# Sheet2.net
KiCad netlist of a schematic drawn in Altium Designer
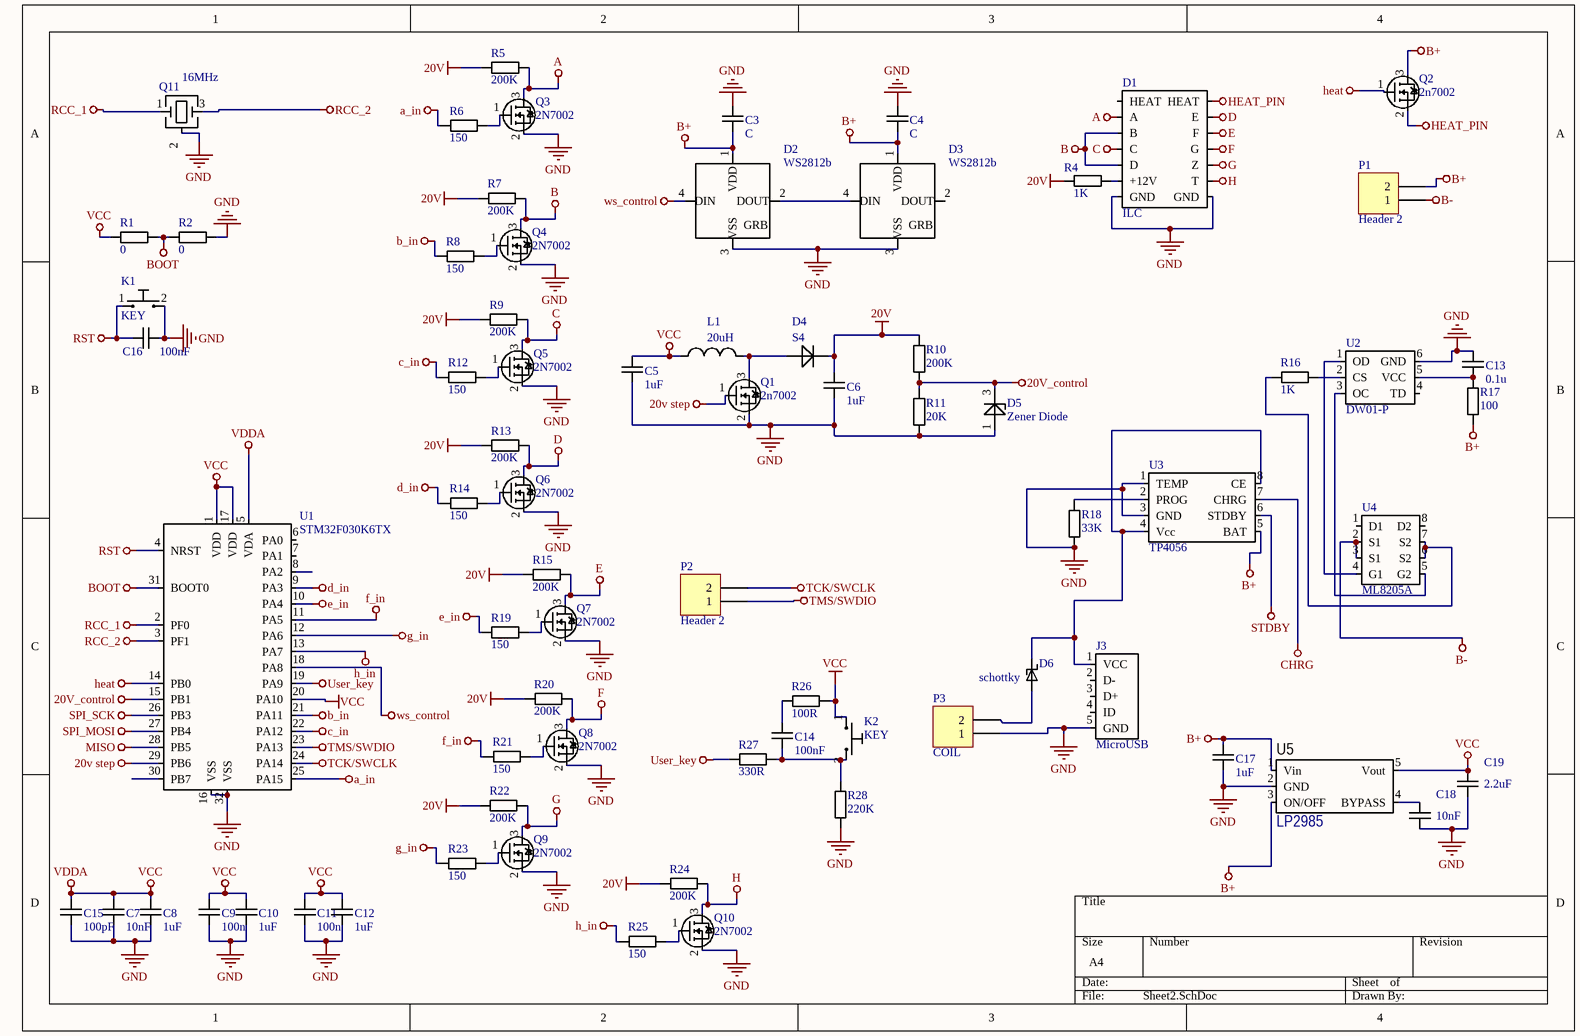
[diagram p0: Sheet2.SchDoc]

(export (version "E")
  (design (tool "Eeschema 10.0.6"))
  (components
    (comp (ref "C3") (value "C") (footprint "SMD-0402C") (libsource (lib "Schlib2") (part "С")))
    (comp (ref "C4") (value "C") (footprint "SMD-0402C") (libsource (lib "Schlib2") (part "С")))
    (comp (ref "C5") (value "1uF") (footprint "SMD-0402C") (libsource (lib "Schlib2") (part "С")))
    (comp (ref "C6") (value "1uF") (footprint "SMD-1206C") (libsource (lib "Schlib2") (part "С")))
    (comp (ref "C7") (value "10nF") (footprint "SMD-0402C") (libsource (lib "Schlib2") (part "С")))
    (comp (ref "C8") (value "1uF") (footprint "SMD-0402C") (libsource (lib "Schlib2") (part "С")))
    (comp (ref "C9") (value "100n") (footprint "SMD-0402C") (libsource (lib "Schlib2") (part "С")))
    (comp (ref "C10") (value "1uF") (footprint "SMD-0402C") (libsource (lib "Schlib2") (part "С")))
    (comp (ref "C11") (value "100n") (footprint "SMD-0402C") (libsource (lib "Schlib2") (part "С")))
    (comp (ref "C12") (value "1uF") (footprint "SMD-0402C") (libsource (lib "Schlib2") (part "С")))
    (comp (ref "C13") (value "0.1u") (footprint "SMD-0402C") (libsource (lib "Schlib2") (part "С")))
    (comp (ref "C14") (value "100nF") (footprint "SMD-0402C") (libsource (lib "Schlib2") (part "С")))
    (comp (ref "C15") (value "100pF") (footprint "SMD-0402C") (libsource (lib "Schlib2") (part "С")))
    (comp (ref "C16") (value "100nF") (footprint "SMD-0402C") (libsource (lib "Schlib2") (part "С")))
    (comp (ref "C17") (value "1uF") (footprint "SMD-0402C") (libsource (lib "Schlib2") (part "С")))
    (comp (ref "C18") (value "10nF") (footprint "SMD-0402C") (libsource (lib "Schlib2") (part "С")))
    (comp (ref "C19") (value "2.2uF") (footprint "SMD-0402C") (libsource (lib "Schlib2") (part "С")))
    (comp (ref "D1") (value "ILC") (footprint "ILC_1") (libsource (lib "Schlib2") (part "ILC-1.9")))
    (comp (ref "D2") (value "WS2812b") (footprint "WS2812b") (libsource (lib "Schlib2") (part "WS2812b")))
    (comp (ref "D3") (value "WS2812b") (footprint "WS2812b") (libsource (lib "Schlib2") (part "WS2812b")))
    (comp (ref "D4") (value "S4") (footprint "S4") (libsource (lib "Schlib2") (part "Diode")))
    (comp (ref "D5") (value "Zener Diode") (footprint "2n7002") (libsource (lib "Schlib2") (part "BZX84")))
    (comp (ref "D6") (value "schottky") (footprint "DO-214AC") (libsource (lib "Schlib2") (part "SS14")))
    (comp (ref "J3")
      (value "MicroUSB")
      (footprint "Micro USB")
      (libsource (lib "Schlib2") (part "Micro_USB_female"))
    )
    (comp (ref "K1") (value "KEY") (footprint "KEY") (libsource (lib "Schlib2") (part "KEY")))
    (comp (ref "K2") (value "KEY") (footprint "KEY") (libsource (lib "Schlib2") (part "KEY")))
    (comp (ref "L1") (value "20uH") (footprint "L_0805") (libsource (lib "Schlib2") (part "L")))
    (comp (ref "P1")
      (value "Header 2")
      (footprint "2pin_battarery")
      (description "Header, 2-Pin")
      (fields (field (name "PUBLISHER") "Altium Limited"))
      (libsource (lib "Miscellaneous Connectors") (part "Header 2"))
    )
    (comp (ref "P2")
      (value "Header 2")
      (footprint "2pin_connector")
      (description "Header, 2-Pin")
      (fields (field (name "PUBLISHER") "Altium Limited"))
      (libsource (lib "Miscellaneous Connectors") (part "Header 2"))
    )
    (comp (ref "P3")
      (value "COIL")
      (footprint "2pin_connector")
      (description "Header, 2-Pin")
      (fields (field (name "PUBLISHER") "Altium Limited"))
      (libsource (lib "Miscellaneous Connectors") (part "Header 2"))
    )
    (comp (ref "Q1") (value "2n7002") (footprint "2n7002") (libsource (lib "Schlib2") (part "2n7002")))
    (comp (ref "Q2") (value "2n7002") (footprint "2n7002") (libsource (lib "Schlib2") (part "2n7002")))
    (comp (ref "Q3") (value "2N7002") (footprint "2n7002") (libsource (lib "Schlib2") (part "2n7002")))
    (comp (ref "Q4") (value "2N7002") (footprint "2n7002") (libsource (lib "Schlib2") (part "2n7002")))
    (comp (ref "Q5") (value "2N7002") (footprint "2n7002") (libsource (lib "Schlib2") (part "2n7002")))
    (comp (ref "Q6") (value "2N7002") (footprint "2n7002") (libsource (lib "Schlib2") (part "2n7002")))
    (comp (ref "Q7") (value "2N7002") (footprint "2n7002") (libsource (lib "Schlib2") (part "2n7002")))
    (comp (ref "Q8") (value "2N7002") (footprint "2n7002") (libsource (lib "Schlib2") (part "2n7002")))
    (comp (ref "Q9") (value "2N7002") (footprint "2n7002") (libsource (lib "Schlib2") (part "2n7002")))
    (comp (ref "Q10") (value "2N7002") (footprint "2n7002") (libsource (lib "Schlib2") (part "2n7002")))
    (comp (ref "Q11")
      (value "16MHz")
      (footprint "Murata Ceramic Resonator")
      (libsource (lib "Schlib2") (part "Crystal_3"))
    )
    (comp (ref "R1") (value "0") (footprint "SMD-0402-RES") (libsource (lib "Schlib2") (part "R")))
    (comp (ref "R2") (value "0") (footprint "SMD-0402-RES") (libsource (lib "Schlib2") (part "R")))
    (comp (ref "R4") (value "1K") (footprint "SMD-0402-RES") (libsource (lib "Schlib2") (part "R")))
    (comp (ref "R5") (value "200K") (footprint "SMD-0402-RES") (libsource (lib "Schlib2") (part "R")))
    (comp (ref "R6") (value "150") (footprint "SMD-0402-RES") (libsource (lib "Schlib2") (part "R")))
    (comp (ref "R7") (value "200K") (footprint "SMD-0402-RES") (libsource (lib "Schlib2") (part "R")))
    (comp (ref "R8") (value "150") (footprint "SMD-0402-RES") (libsource (lib "Schlib2") (part "R")))
    (comp (ref "R9") (value "200K") (footprint "SMD-0402-RES") (libsource (lib "Schlib2") (part "R")))
    (comp (ref "R10") (value "200K") (footprint "SMD-0402-RES") (libsource (lib "Schlib2") (part "R")))
    (comp (ref "R11") (value "20K") (footprint "SMD-0402-RES") (libsource (lib "Schlib2") (part "R")))
    (comp (ref "R12") (value "150") (footprint "SMD-0402-RES") (libsource (lib "Schlib2") (part "R")))
    (comp (ref "R13") (value "200K") (footprint "SMD-0402-RES") (libsource (lib "Schlib2") (part "R")))
    (comp (ref "R14") (value "150") (footprint "SMD-0402-RES") (libsource (lib "Schlib2") (part "R")))
    (comp (ref "R15") (value "200K") (footprint "SMD-0402-RES") (libsource (lib "Schlib2") (part "R")))
    (comp (ref "R16") (value "1K") (footprint "SMD-0402-RES") (libsource (lib "Schlib2") (part "R")))
    (comp (ref "R17") (value "100") (footprint "SMD-0402-RES") (libsource (lib "Schlib2") (part "R")))
    (comp (ref "R18") (value "33K") (footprint "SMD-0402-RES") (libsource (lib "Schlib2") (part "R")))
    (comp (ref "R19") (value "150") (footprint "SMD-0402-RES") (libsource (lib "Schlib2") (part "R")))
    (comp (ref "R20") (value "200K") (footprint "SMD-0402-RES") (libsource (lib "Schlib2") (part "R")))
    (comp (ref "R21") (value "150") (footprint "SMD-0402-RES") (libsource (lib "Schlib2") (part "R")))
    (comp (ref "R22") (value "200K") (footprint "SMD-0402-RES") (libsource (lib "Schlib2") (part "R")))
    (comp (ref "R23") (value "150") (footprint "SMD-0402-RES") (libsource (lib "Schlib2") (part "R")))
    (comp (ref "R24") (value "200K") (footprint "SMD-0402-RES") (libsource (lib "Schlib2") (part "R")))
    (comp (ref "R25") (value "150") (footprint "SMD-0402-RES") (libsource (lib "Schlib2") (part "R")))
    (comp (ref "R26") (value "100R") (footprint "SMD-0402-RES") (libsource (lib "Schlib2") (part "R")))
    (comp (ref "R27") (value "330R") (footprint "SMD-0402-RES") (libsource (lib "Schlib2") (part "R")))
    (comp (ref "R28") (value "220K") (footprint "SMD-0402-RES") (libsource (lib "Schlib2") (part "R")))
    (comp (ref "U1")
      (value "STM32F030K6TX")
      (footprint "LQFP-32")
      (libsource (lib "Schlib2") (part "STM32F030K6TX"))
    )
    (comp (ref "U2") (value "DW01-P") (footprint "SOT-23-6") (libsource (lib "Schlib2") (part "DW01-P")))
    (comp (ref "U3")
      (value "TP4056")
      (footprint "SOIC8")
      (description "1A Standalone Linear Li-lon Battery Charger with Thermal\r\nRegulation in SOP-8")
      (libsource (lib "Schlib2") (part "TP4056"))
    )
    (comp (ref "U4")
      (value "ML8205A")
      (footprint "TSSOP-8")
      (description "The ML8205A uses advanced trench technology to")
      (libsource (lib "Schlib2") (part "ML8205A"))
    )
    (comp (ref "U5") (value "LP2985") (footprint "SOT-23-5") (libsource (lib "Schlib2") (part "LP2985")))
  )
  (nets
    (net (code "1") (name "20V") (class "Default")
      (node (ref "C6") (pin "1") (pinfunction "1_1") (pintype "passive"))
      (node (ref "D4") (pin "2") (pinfunction "2_2") (pintype "passive"))
      (node (ref "R10") (pin "1") (pinfunction "1_1") (pintype "passive"))
      (node (ref "R13") (pin "2") (pinfunction "2_2") (pintype "passive"))
      (node (ref "R15") (pin "2") (pinfunction "2_2") (pintype "passive"))
      (node (ref "R20") (pin "2") (pinfunction "2_2") (pintype "passive"))
      (node (ref "R22") (pin "2") (pinfunction "2_2") (pintype "passive"))
      (node (ref "R24") (pin "2") (pinfunction "2_2") (pintype "passive"))
      (node (ref "R4") (pin "1") (pinfunction "1_1") (pintype "passive"))
      (node (ref "R5") (pin "2") (pinfunction "2_2") (pintype "passive"))
      (node (ref "R7") (pin "2") (pinfunction "2_2") (pintype "passive"))
      (node (ref "R9") (pin "2") (pinfunction "2_2") (pintype "passive"))
    )
    (net (code "2") (name "20V_control") (class "Default")
      (node (ref "D5") (pin "3") (pinfunction "3_3") (pintype "passive"))
      (node (ref "R10") (pin "2") (pinfunction "2_2") (pintype "passive"))
      (node (ref "R11") (pin "2") (pinfunction "2_2") (pintype "passive"))
      (node (ref "U1") (pin "15") (pinfunction "PB1_15") (pintype "passive"))
    )
    (net (code "3") (name "20v step") (class "Default")
      (node (ref "Q1") (pin "1") (pinfunction "1_1") (pintype "passive"))
      (node (ref "U1") (pin "29") (pinfunction "PB6_29") (pintype "passive"))
    )
    (net (code "4") (name "A") (class "Default")
      (node (ref "D1") (pin "2") (pinfunction "A_2") (pintype "passive"))
      (node (ref "Q3") (pin "3") (pinfunction "3_3") (pintype "passive"))
      (node (ref "R5") (pin "1") (pinfunction "1_1") (pintype "passive"))
    )
    (net (code "5") (name "B") (class "Default")
      (node (ref "D1") (pin "3") (pinfunction "B_3") (pintype "passive"))
      (node (ref "D1") (pin "5") (pinfunction "D_5") (pintype "passive"))
      (node (ref "Q4") (pin "3") (pinfunction "3_3") (pintype "passive"))
      (node (ref "R7") (pin "1") (pinfunction "1_1") (pintype "passive"))
    )
    (net (code "6") (name "B+") (class "Default")
      (node (ref "C17") (pin "2") (pinfunction "2_2") (pintype "passive"))
      (node (ref "C3") (pin "1") (pinfunction "1_1") (pintype "passive"))
      (node (ref "C4") (pin "2") (pinfunction "2_2") (pintype "passive"))
      (node (ref "D2") (pin "1") (pinfunction "VDD_1") (pintype "passive"))
      (node (ref "D3") (pin "1") (pinfunction "VDD_1") (pintype "passive"))
      (node (ref "P1") (pin "2") (pinfunction "2_2") (pintype "passive"))
      (node (ref "Q2") (pin "3") (pinfunction "3_3") (pintype "passive"))
      (node (ref "R17") (pin "2") (pinfunction "2_2") (pintype "passive"))
      (node (ref "U3") (pin "5") (pinfunction "BAT_5") (pintype "passive"))
      (node (ref "U5") (pin "1") (pinfunction "Vin_1") (pintype "passive"))
      (node (ref "U5") (pin "3") (pinfunction "ON/OFF_3") (pintype "passive"))
    )
    (net (code "7") (name "B-") (class "Default")
      (node (ref "P1") (pin "1") (pinfunction "1_1") (pintype "passive"))
      (node (ref "U4") (pin "2") (pinfunction "S1_2") (pintype "passive"))
      (node (ref "U4") (pin "3") (pinfunction "S1_3") (pintype "passive"))
    )
    (net (code "8") (name "BOOT") (class "Default")
      (node (ref "R1") (pin "2") (pinfunction "2_2") (pintype "passive"))
      (node (ref "R2") (pin "1") (pinfunction "1_1") (pintype "passive"))
      (node (ref "U1") (pin "31") (pinfunction "BOOT0_31") (pintype "passive"))
    )
    (net (code "9") (name "C") (class "Default")
      (node (ref "D1") (pin "4") (pinfunction "C_4") (pintype "passive"))
      (node (ref "Q5") (pin "3") (pinfunction "3_3") (pintype "passive"))
      (node (ref "R9") (pin "1") (pinfunction "1_1") (pintype "passive"))
    )
    (net (code "10") (name "CHRG") (class "Default")
      (node (ref "U3") (pin "7") (pinfunction "CHRG_7") (pintype "passive"))
    )
    (net (code "11") (name "D") (class "Default")
      (node (ref "D1") (pin "13") (pinfunction "E_13") (pintype "passive"))
      (node (ref "Q6") (pin "3") (pinfunction "3_3") (pintype "passive"))
      (node (ref "R13") (pin "1") (pinfunction "1_1") (pintype "passive"))
    )
    (net (code "12") (name "E") (class "Default")
      (node (ref "D1") (pin "12") (pinfunction "F_12") (pintype "passive"))
      (node (ref "Q7") (pin "3") (pinfunction "3_3") (pintype "passive"))
      (node (ref "R15") (pin "1") (pinfunction "1_1") (pintype "passive"))
    )
    (net (code "13") (name "F") (class "Default")
      (node (ref "D1") (pin "11") (pinfunction "G_11") (pintype "passive"))
      (node (ref "Q8") (pin "3") (pinfunction "3_3") (pintype "passive"))
      (node (ref "R20") (pin "1") (pinfunction "1_1") (pintype "passive"))
    )
    (net (code "14") (name "G") (class "Default")
      (node (ref "D1") (pin "10") (pinfunction "Z_10") (pintype "passive"))
      (node (ref "Q9") (pin "3") (pinfunction "3_3") (pintype "passive"))
      (node (ref "R22") (pin "1") (pinfunction "1_1") (pintype "passive"))
    )
    (net (code "15") (name "GND") (class "Default")
      (node (ref "C10") (pin "1") (pinfunction "1_1") (pintype "passive"))
      (node (ref "C11") (pin "2") (pinfunction "2_2") (pintype "passive"))
      (node (ref "C12") (pin "1") (pinfunction "1_1") (pintype "passive"))
      (node (ref "C13") (pin "2") (pinfunction "2_2") (pintype "passive"))
      (node (ref "C15") (pin "1") (pinfunction "1_1") (pintype "passive"))
      (node (ref "C16") (pin "2") (pinfunction "2_2") (pintype "passive"))
      (node (ref "C17") (pin "1") (pinfunction "1_1") (pintype "passive"))
      (node (ref "C18") (pin "1") (pinfunction "1_1") (pintype "passive"))
      (node (ref "C19") (pin "1") (pinfunction "1_1") (pintype "passive"))
      (node (ref "C3") (pin "2") (pinfunction "2_2") (pintype "passive"))
      (node (ref "C4") (pin "1") (pinfunction "1_1") (pintype "passive"))
      (node (ref "C5") (pin "1") (pinfunction "1_1") (pintype "passive"))
      (node (ref "C6") (pin "2") (pinfunction "2_2") (pintype "passive"))
      (node (ref "C7") (pin "2") (pinfunction "2_2") (pintype "passive"))
      (node (ref "C8") (pin "1") (pinfunction "1_1") (pintype "passive"))
      (node (ref "C9") (pin "2") (pinfunction "2_2") (pintype "passive"))
      (node (ref "D1") (pin "7") (pinfunction "GND_7") (pintype "passive"))
      (node (ref "D1") (pin "8") (pinfunction "GND_8") (pintype "passive"))
      (node (ref "D2") (pin "3") (pinfunction "VSS_3") (pintype "passive"))
      (node (ref "D3") (pin "3") (pinfunction "VSS_3") (pintype "passive"))
      (node (ref "D5") (pin "1") (pinfunction "1_1") (pintype "passive"))
      (node (ref "J3") (pin "5") (pinfunction "GND_5") (pintype "passive"))
      (node (ref "K1") (pin "2") (pinfunction "2_2") (pintype "passive"))
      (node (ref "P3") (pin "1") (pinfunction "1_1") (pintype "passive"))
      (node (ref "Q1") (pin "2") (pinfunction "2_2") (pintype "passive"))
      (node (ref "Q10") (pin "2") (pinfunction "2_2") (pintype "passive"))
      (node (ref "Q11") (pin "2") (pinfunction "2_2") (pintype "passive"))
      (node (ref "Q3") (pin "2") (pinfunction "2_2") (pintype "passive"))
      (node (ref "Q4") (pin "2") (pinfunction "2_2") (pintype "passive"))
      (node (ref "Q5") (pin "2") (pinfunction "2_2") (pintype "passive"))
      (node (ref "Q6") (pin "2") (pinfunction "2_2") (pintype "passive"))
      (node (ref "Q7") (pin "2") (pinfunction "2_2") (pintype "passive"))
      (node (ref "Q8") (pin "2") (pinfunction "2_2") (pintype "passive"))
      (node (ref "Q9") (pin "2") (pinfunction "2_2") (pintype "passive"))
      (node (ref "R11") (pin "1") (pinfunction "1_1") (pintype "passive"))
      (node (ref "R18") (pin "1") (pinfunction "1_1") (pintype "passive"))
      (node (ref "R2") (pin "2") (pinfunction "2_2") (pintype "passive"))
      (node (ref "R28") (pin "1") (pinfunction "1_1") (pintype "passive"))
      (node (ref "U1") (pin "16") (pinfunction "VSS_16") (pintype "passive"))
      (node (ref "U1") (pin "32") (pinfunction "VSS_32") (pintype "passive"))
      (node (ref "U2") (pin "6") (pinfunction "GND_6") (pintype "passive"))
      (node (ref "U3") (pin "1") (pinfunction "TEMP_1") (pintype "passive"))
      (node (ref "U3") (pin "3") (pinfunction "GND_3") (pintype "passive"))
      (node (ref "U5") (pin "2") (pinfunction "GND_2") (pintype "passive"))
    )
    (net (code "16") (name "H") (class "Default")
      (node (ref "D1") (pin "9") (pinfunction "T_9") (pintype "passive"))
      (node (ref "Q10") (pin "3") (pinfunction "3_3") (pintype "passive"))
      (node (ref "R24") (pin "1") (pinfunction "1_1") (pintype "passive"))
    )
    (net (code "17") (name "HEAT_PIN") (class "Default")
      (node (ref "D1") (pin "14") (pinfunction "HEAT_14") (pintype "passive"))
      (node (ref "Q2") (pin "2") (pinfunction "2_2") (pintype "passive"))
    )
    (net (code "18") (name "MISO") (class "Default")
      (node (ref "U1") (pin "28") (pinfunction "PB5_28") (pintype "passive"))
    )
    (net (code "19") (name "Net-(C14-Pad1)") (class "Default")
      (node (ref "C14") (pin "1") (pinfunction "1_1") (pintype "passive"))
      (node (ref "K2") (pin "2") (pinfunction "2_2") (pintype "passive"))
      (node (ref "R27") (pin "2") (pinfunction "2_2") (pintype "passive"))
      (node (ref "R28") (pin "2") (pinfunction "2_2") (pintype "passive"))
    )
    (net (code "20") (name "Net-(C14-Pad2)") (class "Default")
      (node (ref "C14") (pin "2") (pinfunction "2_2") (pintype "passive"))
      (node (ref "R26") (pin "1") (pinfunction "1_1") (pintype "passive"))
    )
    (net (code "21") (name "Net-(D1-+12V)") (class "Default")
      (node (ref "D1") (pin "6") (pinfunction "+12V_6") (pintype "passive"))
      (node (ref "R4") (pin "2") (pinfunction "2_2") (pintype "passive"))
    )
    (net (code "22") (name "Net-(D2-DOUT)") (class "Default")
      (node (ref "D2") (pin "2") (pinfunction "DOUT_2") (pintype "passive"))
      (node (ref "D3") (pin "4") (pinfunction "DIN_4") (pintype "passive"))
    )
    (net (code "23") (name "Net-(D4-Pad1)") (class "Default")
      (node (ref "D4") (pin "1") (pinfunction "1_1") (pintype "passive"))
      (node (ref "L1") (pin "2") (pinfunction "2_2") (pintype "passive"))
      (node (ref "Q1") (pin "3") (pinfunction "3_3") (pintype "passive"))
    )
    (net (code "24") (name "Net-(D6-PadA)") (class "Default")
      (node (ref "D6") (pin "A") (pinfunction "A_A") (pintype "passive"))
      (node (ref "P3") (pin "2") (pinfunction "2_2") (pintype "passive"))
    )
    (net (code "25") (name "Net-(J3-VCC)") (class "Default")
      (node (ref "D6") (pin "K") (pinfunction "K_K") (pintype "passive"))
      (node (ref "J3") (pin "1") (pinfunction "VCC_1") (pintype "passive"))
      (node (ref "U3") (pin "4") (pinfunction "Vcc_4") (pintype "passive"))
      (node (ref "U3") (pin "8") (pinfunction "CE_8") (pintype "passive"))
    )
    (net (code "26") (name "Net-(Q3-Pad1)") (class "Default")
      (node (ref "Q3") (pin "1") (pinfunction "1_1") (pintype "passive"))
      (node (ref "R6") (pin "1") (pinfunction "1_1") (pintype "passive"))
    )
    (net (code "27") (name "Net-(Q4-Pad1)") (class "Default")
      (node (ref "Q4") (pin "1") (pinfunction "1_1") (pintype "passive"))
      (node (ref "R8") (pin "1") (pinfunction "1_1") (pintype "passive"))
    )
    (net (code "28") (name "Net-(Q5-Pad1)") (class "Default")
      (node (ref "Q5") (pin "1") (pinfunction "1_1") (pintype "passive"))
      (node (ref "R12") (pin "1") (pinfunction "1_1") (pintype "passive"))
    )
    (net (code "29") (name "Net-(Q6-Pad1)") (class "Default")
      (node (ref "Q6") (pin "1") (pinfunction "1_1") (pintype "passive"))
      (node (ref "R14") (pin "1") (pinfunction "1_1") (pintype "passive"))
    )
    (net (code "30") (name "Net-(Q7-Pad1)") (class "Default")
      (node (ref "Q7") (pin "1") (pinfunction "1_1") (pintype "passive"))
      (node (ref "R19") (pin "1") (pinfunction "1_1") (pintype "passive"))
    )
    (net (code "31") (name "Net-(Q8-Pad1)") (class "Default")
      (node (ref "Q8") (pin "1") (pinfunction "1_1") (pintype "passive"))
      (node (ref "R21") (pin "1") (pinfunction "1_1") (pintype "passive"))
    )
    (net (code "32") (name "Net-(Q9-Pad1)") (class "Default")
      (node (ref "Q9") (pin "1") (pinfunction "1_1") (pintype "passive"))
      (node (ref "R23") (pin "1") (pinfunction "1_1") (pintype "passive"))
    )
    (net (code "33") (name "Net-(Q10-Pad1)") (class "Default")
      (node (ref "Q10") (pin "1") (pinfunction "1_1") (pintype "passive"))
      (node (ref "R25") (pin "1") (pinfunction "1_1") (pintype "passive"))
    )
    (net (code "34") (name "Net-(R16-Pad2)") (class "Default")
      (node (ref "R16") (pin "2") (pinfunction "2_2") (pintype "passive"))
      (node (ref "U4") (pin "6") (pinfunction "S2_6") (pintype "passive"))
      (node (ref "U4") (pin "7") (pinfunction "S2_7") (pintype "passive"))
    )
    (net (code "35") (name "Net-(U2-CS)") (class "Default")
      (node (ref "R16") (pin "1") (pinfunction "1_1") (pintype "passive"))
      (node (ref "U2") (pin "2") (pinfunction "CS_2") (pintype "passive"))
    )
    (net (code "36") (name "Net-(U2-OC)") (class "Default")
      (node (ref "U2") (pin "3") (pinfunction "OC_3") (pintype "passive"))
      (node (ref "U4") (pin "5") (pinfunction "G2_5") (pintype "passive"))
    )
    (net (code "37") (name "Net-(U2-OD)") (class "Default")
      (node (ref "U2") (pin "1") (pinfunction "OD_1") (pintype "passive"))
      (node (ref "U4") (pin "4") (pinfunction "G1_4") (pintype "passive"))
    )
    (net (code "38") (name "Net-(U2-VCC)") (class "Default")
      (node (ref "C13") (pin "1") (pinfunction "1_1") (pintype "passive"))
      (node (ref "R17") (pin "1") (pinfunction "1_1") (pintype "passive"))
      (node (ref "U2") (pin "5") (pinfunction "VCC_5") (pintype "passive"))
    )
    (net (code "39") (name "Net-(U3-PROG)") (class "Default")
      (node (ref "R18") (pin "2") (pinfunction "2_2") (pintype "passive"))
      (node (ref "U3") (pin "2") (pinfunction "PROG_2") (pintype "passive"))
    )
    (net (code "40") (name "Net-(U5-BYPASS)") (class "Default")
      (node (ref "C18") (pin "2") (pinfunction "2_2") (pintype "passive"))
      (node (ref "U5") (pin "4") (pinfunction "BYPASS_4") (pintype "passive"))
    )
    (net (code "41") (name "RCC_1") (class "Default")
      (node (ref "Q11") (pin "1") (pinfunction "1_1") (pintype "passive"))
      (node (ref "U1") (pin "2") (pinfunction "PF0_2") (pintype "passive"))
    )
    (net (code "42") (name "RCC_2") (class "Default")
      (node (ref "Q11") (pin "3") (pinfunction "3_3") (pintype "passive"))
      (node (ref "U1") (pin "3") (pinfunction "PF1_3") (pintype "passive"))
    )
    (net (code "43") (name "RST") (class "Default")
      (node (ref "C16") (pin "1") (pinfunction "1_1") (pintype "passive"))
      (node (ref "K1") (pin "1") (pinfunction "1_1") (pintype "passive"))
      (node (ref "U1") (pin "4") (pinfunction "NRST_4") (pintype "passive"))
    )
    (net (code "44") (name "SPI_MOSI") (class "Default")
      (node (ref "U1") (pin "27") (pinfunction "PB4_27") (pintype "passive"))
    )
    (net (code "45") (name "SPI_SCK") (class "Default")
      (node (ref "U1") (pin "26") (pinfunction "PB3_26") (pintype "passive"))
    )
    (net (code "46") (name "STDBY") (class "Default")
      (node (ref "U3") (pin "6") (pinfunction "STDBY_6") (pintype "passive"))
    )
    (net (code "47") (name "TCK{slash}SWCLK") (class "Default")
      (node (ref "P2") (pin "2") (pinfunction "2_2") (pintype "passive"))
      (node (ref "U1") (pin "24") (pinfunction "PA14_24") (pintype "passive"))
    )
    (net (code "48") (name "TMS{slash}SWDIO") (class "Default")
      (node (ref "P2") (pin "1") (pinfunction "1_1") (pintype "passive"))
      (node (ref "U1") (pin "23") (pinfunction "PA13_23") (pintype "passive"))
    )
    (net (code "49") (name "User_key") (class "Default")
      (node (ref "R27") (pin "1") (pinfunction "1_1") (pintype "passive"))
      (node (ref "U1") (pin "19") (pinfunction "PA9_19") (pintype "passive"))
    )
    (net (code "50") (name "VCC") (class "Default")
      (node (ref "C10") (pin "2") (pinfunction "2_2") (pintype "passive"))
      (node (ref "C11") (pin "1") (pinfunction "1_1") (pintype "passive"))
      (node (ref "C12") (pin "2") (pinfunction "2_2") (pintype "passive"))
      (node (ref "C15") (pin "2") (pinfunction "2_2") (pintype "passive"))
      (node (ref "C19") (pin "2") (pinfunction "2_2") (pintype "passive"))
      (node (ref "C5") (pin "2") (pinfunction "2_2") (pintype "passive"))
      (node (ref "C7") (pin "1") (pinfunction "1_1") (pintype "passive"))
      (node (ref "C8") (pin "2") (pinfunction "2_2") (pintype "passive"))
      (node (ref "C9") (pin "1") (pinfunction "1_1") (pintype "passive"))
      (node (ref "K2") (pin "1") (pinfunction "1_1") (pintype "passive"))
      (node (ref "L1") (pin "1") (pinfunction "4_1") (pintype "passive"))
      (node (ref "R1") (pin "1") (pinfunction "1_1") (pintype "passive"))
      (node (ref "R26") (pin "2") (pinfunction "2_2") (pintype "passive"))
      (node (ref "U1") (pin "1") (pinfunction "VDD_1") (pintype "passive"))
      (node (ref "U1") (pin "17") (pinfunction "VDD_17") (pintype "passive"))
      (node (ref "U1") (pin "20") (pinfunction "PA10_20") (pintype "passive"))
      (node (ref "U1") (pin "5") (pinfunction "VDA_5") (pintype "passive"))
      (node (ref "U5") (pin "5") (pinfunction "Vout_5") (pintype "passive"))
    )
    (net (code "51") (name "a_in") (class "Default")
      (node (ref "R6") (pin "2") (pinfunction "2_2") (pintype "passive"))
      (node (ref "U1") (pin "25") (pinfunction "PA15_25") (pintype "passive"))
    )
    (net (code "52") (name "b_in") (class "Default")
      (node (ref "R8") (pin "2") (pinfunction "2_2") (pintype "passive"))
      (node (ref "U1") (pin "21") (pinfunction "PA11_21") (pintype "passive"))
    )
    (net (code "53") (name "c_in") (class "Default")
      (node (ref "R12") (pin "2") (pinfunction "2_2") (pintype "passive"))
      (node (ref "U1") (pin "22") (pinfunction "PA12_22") (pintype "passive"))
    )
    (net (code "54") (name "d_in") (class "Default")
      (node (ref "R14") (pin "2") (pinfunction "2_2") (pintype "passive"))
      (node (ref "U1") (pin "9") (pinfunction "PA3_9") (pintype "passive"))
    )
    (net (code "55") (name "e_in") (class "Default")
      (node (ref "R19") (pin "2") (pinfunction "2_2") (pintype "passive"))
      (node (ref "U1") (pin "10") (pinfunction "PA4_10") (pintype "passive"))
    )
    (net (code "56") (name "f_in") (class "Default")
      (node (ref "R21") (pin "2") (pinfunction "2_2") (pintype "passive"))
      (node (ref "U1") (pin "11") (pinfunction "PA5_11") (pintype "passive"))
    )
    (net (code "57") (name "g_in") (class "Default")
      (node (ref "R23") (pin "2") (pinfunction "2_2") (pintype "passive"))
      (node (ref "U1") (pin "12") (pinfunction "PA6_12") (pintype "passive"))
    )
    (net (code "58") (name "h_in") (class "Default")
      (node (ref "R25") (pin "2") (pinfunction "2_2") (pintype "passive"))
      (node (ref "U1") (pin "13") (pinfunction "PA7_13") (pintype "passive"))
    )
    (net (code "59") (name "heat") (class "Default")
      (node (ref "Q2") (pin "1") (pinfunction "1_1") (pintype "passive"))
      (node (ref "U1") (pin "14") (pinfunction "PB0_14") (pintype "passive"))
    )
    (net (code "60") (name "unconnected-(D1-HEAT-Pad1)") (class "Default")
      (node (ref "D1") (pin "1") (pinfunction "HEAT_1") (pintype "passive"))
    )
    (net (code "61") (name "unconnected-(D3-DOUT-Pad2)") (class "Default")
      (node (ref "D3") (pin "2") (pinfunction "DOUT_2") (pintype "passive"))
    )
    (net (code "62") (name "unconnected-(J3-D+-Pad3)") (class "Default")
      (node (ref "J3") (pin "3") (pinfunction "D+_3") (pintype "passive"))
    )
    (net (code "63") (name "unconnected-(J3-D--Pad2)") (class "Default")
      (node (ref "J3") (pin "2") (pinfunction "D-_2") (pintype "passive"))
    )
    (net (code "64") (name "unconnected-(J3-ID-Pad4)") (class "Default")
      (node (ref "J3") (pin "4") (pinfunction "ID_4") (pintype "passive"))
    )
    (net (code "65") (name "unconnected-(U1-PA0-Pad6)") (class "Default")
      (node (ref "U1") (pin "6") (pinfunction "PA0_6") (pintype "passive"))
    )
    (net (code "66") (name "unconnected-(U1-PA1-Pad7)") (class "Default")
      (node (ref "U1") (pin "7") (pinfunction "PA1_7") (pintype "passive"))
    )
    (net (code "67") (name "unconnected-(U1-PA2-Pad8)") (class "Default")
      (node (ref "U1") (pin "8") (pinfunction "PA2_8") (pintype "passive"))
    )
    (net (code "68") (name "unconnected-(U1-PB7-Pad30)") (class "Default")
      (node (ref "U1") (pin "30") (pinfunction "PB7_30") (pintype "passive"))
    )
    (net (code "69") (name "unconnected-(U2-TD-Pad4)") (class "Default")
      (node (ref "U2") (pin "4") (pinfunction "TD_4") (pintype "passive"))
    )
    (net (code "70") (name "unconnected-(U4-D1-Pad1)") (class "Default")
      (node (ref "U4") (pin "1") (pinfunction "D1_1") (pintype "passive"))
    )
    (net (code "71") (name "unconnected-(U4-D2-Pad8)") (class "Default")
      (node (ref "U4") (pin "8") (pinfunction "D2_8") (pintype "passive"))
    )
    (net (code "72") (name "ws_control") (class "Default")
      (node (ref "D2") (pin "4") (pinfunction "DIN_4") (pintype "passive"))
      (node (ref "U1") (pin "18") (pinfunction "PA8_18") (pintype "passive"))
    )
  )
)
